# Reinhard.net
KiCad netlist of a schematic drawn in EAGLE
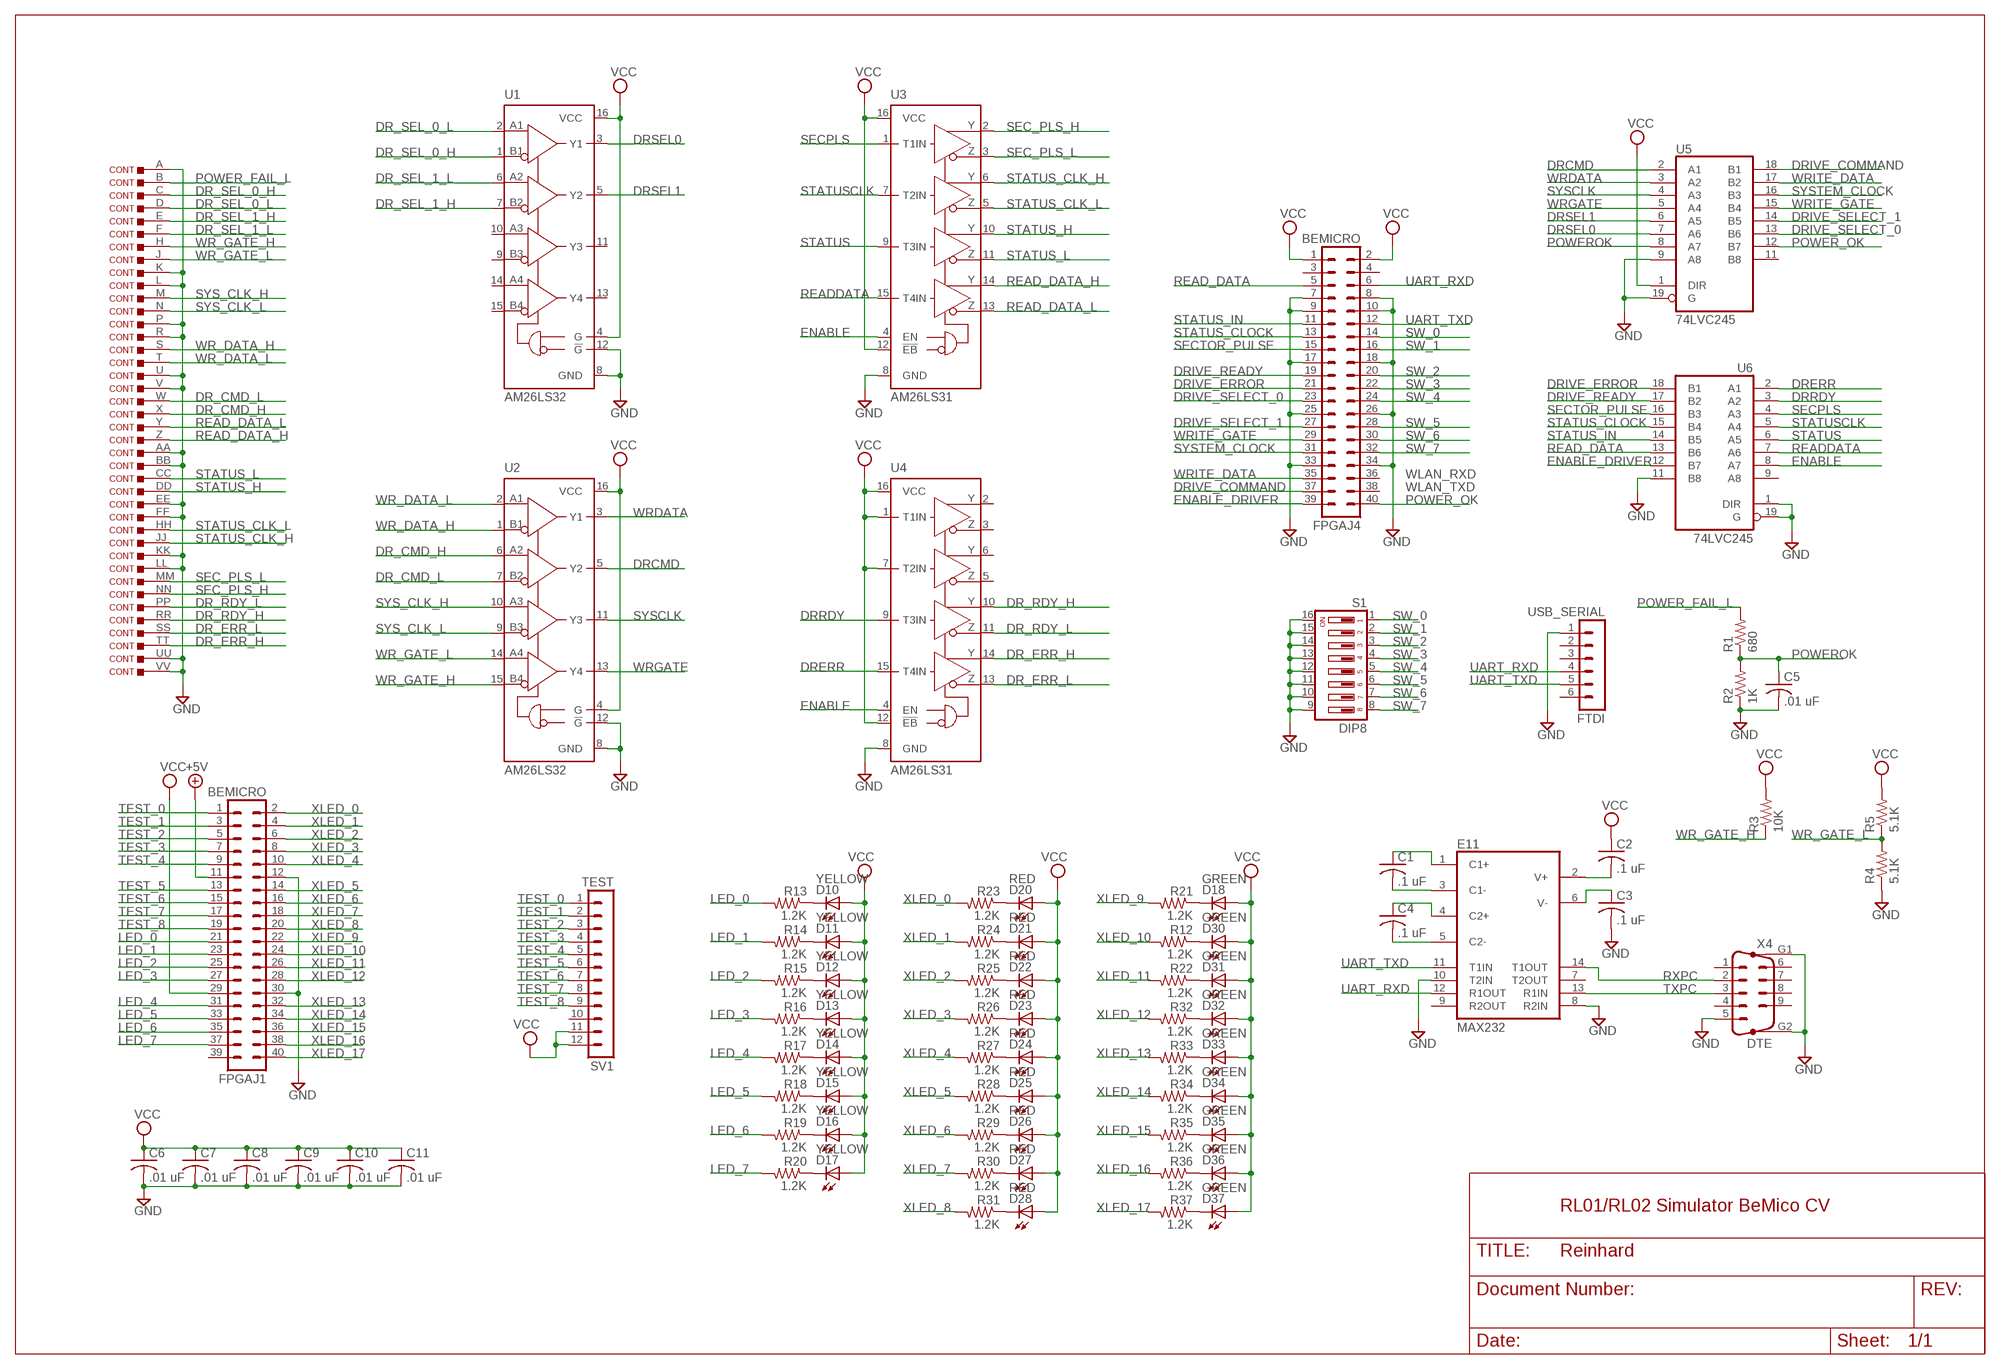
[diagram p0: schematic, sheet 1]

(export (version "E")
  (design (tool "Eeschema 10.0.6"))
  (components
    (comp (ref "C1")
      (value ".1 uF")
      (footprint "eagle-import:C050-025X075")
      (libsource (lib "eagle-import") (part "C-US050-025X075"))
    )
    (comp (ref "C2")
      (value ".1 uF")
      (footprint "eagle-import:C050-025X075")
      (libsource (lib "eagle-import") (part "C-US050-025X075"))
    )
    (comp (ref "C3")
      (value ".1 uF")
      (footprint "eagle-import:C050-025X075")
      (libsource (lib "eagle-import") (part "C-US050-025X075"))
    )
    (comp (ref "C4")
      (value ".1 uF")
      (footprint "eagle-import:C050-025X075")
      (libsource (lib "eagle-import") (part "C-US050-025X075"))
    )
    (comp (ref "C5")
      (value ".01 uF")
      (footprint "eagle-import:C050-025X075")
      (libsource (lib "eagle-import") (part "C-US050-025X075"))
    )
    (comp (ref "C6")
      (value ".01 uF")
      (footprint "eagle-import:C050-025X075")
      (libsource (lib "eagle-import") (part "C-US050-025X075"))
    )
    (comp (ref "C7")
      (value ".01 uF")
      (footprint "eagle-import:C050-025X075")
      (libsource (lib "eagle-import") (part "C-US050-025X075"))
    )
    (comp (ref "C8")
      (value ".01 uF")
      (footprint "eagle-import:C050-025X075")
      (libsource (lib "eagle-import") (part "C-US050-025X075"))
    )
    (comp (ref "C9")
      (value ".01 uF")
      (footprint "eagle-import:C050-025X075")
      (libsource (lib "eagle-import") (part "C-US050-025X075"))
    )
    (comp (ref "C10")
      (value ".01 uF")
      (footprint "eagle-import:C050-025X075")
      (libsource (lib "eagle-import") (part "C-US050-025X075"))
    )
    (comp (ref "C11")
      (value ".01 uF")
      (footprint "eagle-import:C050-025X075")
      (libsource (lib "eagle-import") (part "C-US050-025X075"))
    )
    (comp (ref "CONT")
      (value "DEC40PINSV")
      (footprint "eagle-import:DEC40PINV")
      (libsource (lib "eagle-import") (part "DEC40PINSV"))
    )
    (comp (ref "D10")
      (value "YELLOW")
      (footprint "eagle-import:LED3MM")
      (libsource (lib "eagle-import") (part "LED3MM"))
    )
    (comp (ref "D11")
      (value "YELLOW")
      (footprint "eagle-import:LED3MM")
      (libsource (lib "eagle-import") (part "LED3MM"))
    )
    (comp (ref "D12")
      (value "YELLOW")
      (footprint "eagle-import:LED3MM")
      (libsource (lib "eagle-import") (part "LED3MM"))
    )
    (comp (ref "D13")
      (value "YELLOW")
      (footprint "eagle-import:LED3MM")
      (libsource (lib "eagle-import") (part "LED3MM"))
    )
    (comp (ref "D14")
      (value "YELLOW")
      (footprint "eagle-import:LED3MM")
      (libsource (lib "eagle-import") (part "LED3MM"))
    )
    (comp (ref "D15")
      (value "YELLOW")
      (footprint "eagle-import:LED3MM")
      (libsource (lib "eagle-import") (part "LED3MM"))
    )
    (comp (ref "D16")
      (value "YELLOW")
      (footprint "eagle-import:LED3MM")
      (libsource (lib "eagle-import") (part "LED3MM"))
    )
    (comp (ref "D17")
      (value "YELLOW")
      (footprint "eagle-import:LED3MM")
      (libsource (lib "eagle-import") (part "LED3MM"))
    )
    (comp (ref "D18")
      (value "GREEN")
      (footprint "eagle-import:LED3MM")
      (libsource (lib "eagle-import") (part "LED3MM"))
    )
    (comp (ref "D20")
      (value "RED")
      (footprint "eagle-import:LED3MM")
      (libsource (lib "eagle-import") (part "LED3MM"))
    )
    (comp (ref "D21")
      (value "RED")
      (footprint "eagle-import:LED3MM")
      (libsource (lib "eagle-import") (part "LED3MM"))
    )
    (comp (ref "D22")
      (value "RED")
      (footprint "eagle-import:LED3MM")
      (libsource (lib "eagle-import") (part "LED3MM"))
    )
    (comp (ref "D23")
      (value "RED")
      (footprint "eagle-import:LED3MM")
      (libsource (lib "eagle-import") (part "LED3MM"))
    )
    (comp (ref "D24")
      (value "RED")
      (footprint "eagle-import:LED3MM")
      (libsource (lib "eagle-import") (part "LED3MM"))
    )
    (comp (ref "D25")
      (value "RED")
      (footprint "eagle-import:LED3MM")
      (libsource (lib "eagle-import") (part "LED3MM"))
    )
    (comp (ref "D26")
      (value "RED")
      (footprint "eagle-import:LED3MM")
      (libsource (lib "eagle-import") (part "LED3MM"))
    )
    (comp (ref "D27")
      (value "RED")
      (footprint "eagle-import:LED3MM")
      (libsource (lib "eagle-import") (part "LED3MM"))
    )
    (comp (ref "D28")
      (value "RED")
      (footprint "eagle-import:LED3MM")
      (libsource (lib "eagle-import") (part "LED3MM"))
    )
    (comp (ref "D30")
      (value "GREEN")
      (footprint "eagle-import:LED3MM")
      (libsource (lib "eagle-import") (part "LED3MM"))
    )
    (comp (ref "D31")
      (value "GREEN")
      (footprint "eagle-import:LED3MM")
      (libsource (lib "eagle-import") (part "LED3MM"))
    )
    (comp (ref "D32")
      (value "GREEN")
      (footprint "eagle-import:LED3MM")
      (libsource (lib "eagle-import") (part "LED3MM"))
    )
    (comp (ref "D33")
      (value "GREEN")
      (footprint "eagle-import:LED3MM")
      (libsource (lib "eagle-import") (part "LED3MM"))
    )
    (comp (ref "D34")
      (value "GREEN")
      (footprint "eagle-import:LED3MM")
      (libsource (lib "eagle-import") (part "LED3MM"))
    )
    (comp (ref "D35")
      (value "GREEN")
      (footprint "eagle-import:LED3MM")
      (libsource (lib "eagle-import") (part "LED3MM"))
    )
    (comp (ref "D36")
      (value "GREEN")
      (footprint "eagle-import:LED3MM")
      (libsource (lib "eagle-import") (part "LED3MM"))
    )
    (comp (ref "D37")
      (value "GREEN")
      (footprint "eagle-import:LED3MM")
      (libsource (lib "eagle-import") (part "LED3MM"))
    )
    (comp (ref "E11")
      (value "MAX232")
      (footprint "eagle-import:DIL16")
      (fields (field (name "MF") "MAXIM") (field (name "MPN") "MAX232ACPE+"))
      (libsource (lib "eagle-import") (part "MAX232"))
    )
    (comp (ref "FPGAJ1")
      (value "BEMICRO")
      (footprint "eagle-import:MA20-2")
      (libsource (lib "eagle-import") (part "MA20-2"))
    )
    (comp (ref "FPGAJ4")
      (value "BEMICRO")
      (footprint "eagle-import:MA20-2")
      (libsource (lib "eagle-import") (part "MA20-2"))
    )
    (comp (ref "FTDI")
      (value "USB_SERIAL")
      (footprint "eagle-import:MA06-1")
      (libsource (lib "eagle-import") (part "MA06-1"))
    )
    (comp (ref "R1")
      (value "680")
      (footprint "eagle-import:0207_10")
      (libsource (lib "eagle-import") (part "R-US_0207/10"))
    )
    (comp (ref "R2")
      (value "1K")
      (footprint "eagle-import:0207_10")
      (libsource (lib "eagle-import") (part "R-US_0207/10"))
    )
    (comp (ref "R3")
      (value "10K")
      (footprint "eagle-import:0207_10")
      (libsource (lib "eagle-import") (part "R-US_0207/10"))
    )
    (comp (ref "R4")
      (value "5.1K")
      (footprint "eagle-import:0207_10")
      (libsource (lib "eagle-import") (part "R-US_0207/10"))
    )
    (comp (ref "R5")
      (value "5.1K")
      (footprint "eagle-import:0207_10")
      (libsource (lib "eagle-import") (part "R-US_0207/10"))
    )
    (comp (ref "R12")
      (value "1.2K")
      (footprint "eagle-import:0207_10")
      (libsource (lib "eagle-import") (part "R-US_0207/10"))
    )
    (comp (ref "R13")
      (value "1.2K")
      (footprint "eagle-import:0207_10")
      (libsource (lib "eagle-import") (part "R-US_0207/10"))
    )
    (comp (ref "R14")
      (value "1.2K")
      (footprint "eagle-import:0207_10")
      (libsource (lib "eagle-import") (part "R-US_0207/10"))
    )
    (comp (ref "R15")
      (value "1.2K")
      (footprint "eagle-import:0207_10")
      (libsource (lib "eagle-import") (part "R-US_0207/10"))
    )
    (comp (ref "R16")
      (value "1.2K")
      (footprint "eagle-import:0207_10")
      (libsource (lib "eagle-import") (part "R-US_0207/10"))
    )
    (comp (ref "R17")
      (value "1.2K")
      (footprint "eagle-import:0207_10")
      (libsource (lib "eagle-import") (part "R-US_0207/10"))
    )
    (comp (ref "R18")
      (value "1.2K")
      (footprint "eagle-import:0207_10")
      (libsource (lib "eagle-import") (part "R-US_0207/10"))
    )
    (comp (ref "R19")
      (value "1.2K")
      (footprint "eagle-import:0207_10")
      (libsource (lib "eagle-import") (part "R-US_0207/10"))
    )
    (comp (ref "R20")
      (value "1.2K")
      (footprint "eagle-import:0207_10")
      (libsource (lib "eagle-import") (part "R-US_0207/10"))
    )
    (comp (ref "R21")
      (value "1.2K")
      (footprint "eagle-import:0207_10")
      (libsource (lib "eagle-import") (part "R-US_0207/10"))
    )
    (comp (ref "R22")
      (value "1.2K")
      (footprint "eagle-import:0207_10")
      (libsource (lib "eagle-import") (part "R-US_0207/10"))
    )
    (comp (ref "R23")
      (value "1.2K")
      (footprint "eagle-import:0207_10")
      (libsource (lib "eagle-import") (part "R-US_0207/10"))
    )
    (comp (ref "R24")
      (value "1.2K")
      (footprint "eagle-import:0207_10")
      (libsource (lib "eagle-import") (part "R-US_0207/10"))
    )
    (comp (ref "R25")
      (value "1.2K")
      (footprint "eagle-import:0207_10")
      (libsource (lib "eagle-import") (part "R-US_0207/10"))
    )
    (comp (ref "R26")
      (value "1.2K")
      (footprint "eagle-import:0207_10")
      (libsource (lib "eagle-import") (part "R-US_0207/10"))
    )
    (comp (ref "R27")
      (value "1.2K")
      (footprint "eagle-import:0207_10")
      (libsource (lib "eagle-import") (part "R-US_0207/10"))
    )
    (comp (ref "R28")
      (value "1.2K")
      (footprint "eagle-import:0207_10")
      (libsource (lib "eagle-import") (part "R-US_0207/10"))
    )
    (comp (ref "R29")
      (value "1.2K")
      (footprint "eagle-import:0207_10")
      (libsource (lib "eagle-import") (part "R-US_0207/10"))
    )
    (comp (ref "R30")
      (value "1.2K")
      (footprint "eagle-import:0207_10")
      (libsource (lib "eagle-import") (part "R-US_0207/10"))
    )
    (comp (ref "R31")
      (value "1.2K")
      (footprint "eagle-import:0207_10")
      (libsource (lib "eagle-import") (part "R-US_0207/10"))
    )
    (comp (ref "R32")
      (value "1.2K")
      (footprint "eagle-import:0207_10")
      (libsource (lib "eagle-import") (part "R-US_0207/10"))
    )
    (comp (ref "R33")
      (value "1.2K")
      (footprint "eagle-import:0207_10")
      (libsource (lib "eagle-import") (part "R-US_0207/10"))
    )
    (comp (ref "R34")
      (value "1.2K")
      (footprint "eagle-import:0207_10")
      (libsource (lib "eagle-import") (part "R-US_0207/10"))
    )
    (comp (ref "R35")
      (value "1.2K")
      (footprint "eagle-import:0207_10")
      (libsource (lib "eagle-import") (part "R-US_0207/10"))
    )
    (comp (ref "R36")
      (value "1.2K")
      (footprint "eagle-import:0207_10")
      (libsource (lib "eagle-import") (part "R-US_0207/10"))
    )
    (comp (ref "R37")
      (value "1.2K")
      (footprint "eagle-import:0207_10")
      (libsource (lib "eagle-import") (part "R-US_0207/10"))
    )
    (comp (ref "S1")
      (value "DIP8")
      (footprint "eagle-import:DIP08YL")
      (libsource (lib "eagle-import") (part "DIP08YL"))
    )
    (comp (ref "SV1")
      (value "TEST")
      (footprint "eagle-import:MA12-1")
      (libsource (lib "eagle-import") (part "MA12-1"))
    )
    (comp (ref "U1")
      (value "AM26LS32")
      (footprint "eagle-import:DIL16")
      (fields (field (name "MF") "MAXIM") (field (name "MPN") "MAX3095CPE+"))
      (libsource (lib "eagle-import") (part "MAX309PE5C"))
    )
    (comp (ref "U2")
      (value "AM26LS32")
      (footprint "eagle-import:DIL16")
      (fields (field (name "MF") "MAXIM") (field (name "MPN") "MAX3095CPE+"))
      (libsource (lib "eagle-import") (part "MAX309PE5C"))
    )
    (comp (ref "U3")
      (value "AM26LS31")
      (footprint "eagle-import:DIL16")
      (libsource (lib "eagle-import") (part "MAX304"))
    )
    (comp (ref "U4")
      (value "AM26LS31")
      (footprint "eagle-import:DIL16")
      (libsource (lib "eagle-import") (part "MAX304"))
    )
    (comp (ref "U5")
      (value "74LVC245")
      (footprint "eagle-import:DIL20")
      (libsource (lib "eagle-import") (part "74245NLS"))
    )
    (comp (ref "U6")
      (value "74LVC245")
      (footprint "eagle-import:DIL20")
      (libsource (lib "eagle-import") (part "74245NLS"))
    )
    (comp (ref "X4")
      (value "DTE")
      (footprint "eagle-import:M09HP")
      (libsource (lib "eagle-import") (part "M09HP"))
    )
  )
  (nets
    (net (code "1") (name "+5V") (class "Default")
      (node (ref "FPGAJ1") (pin "11") (pinfunction "11_11") (pintype "passive"))
    )
    (net (code "2") (name "/DRCMD") (class "Default")
      (node (ref "U2") (pin "5") (pinfunction "Y2_5") (pintype "output"))
      (node (ref "U5") (pin "2") (pinfunction "A1_2") (pintype "bidirectional"))
    )
    (net (code "3") (name "/DRERR") (class "Default")
      (node (ref "U4") (pin "15") (pinfunction "T4IN_15") (pintype "input"))
      (node (ref "U6") (pin "2") (pinfunction "A1_2") (pintype "bidirectional"))
    )
    (net (code "4") (name "/DRIVE_COMMAND") (class "Default")
      (node (ref "FPGAJ4") (pin "37") (pinfunction "37_37") (pintype "passive"))
      (node (ref "U5") (pin "18") (pinfunction "B1_18") (pintype "bidirectional"))
    )
    (net (code "5") (name "/DRIVE_ERROR") (class "Default")
      (node (ref "FPGAJ4") (pin "21") (pinfunction "21_21") (pintype "passive"))
      (node (ref "U6") (pin "18") (pinfunction "B1_18") (pintype "bidirectional"))
    )
    (net (code "6") (name "/DRIVE_READY") (class "Default")
      (node (ref "FPGAJ4") (pin "19") (pinfunction "19_19") (pintype "passive"))
      (node (ref "U6") (pin "17") (pinfunction "B2_17") (pintype "bidirectional"))
    )
    (net (code "7") (name "/DRIVE_SELECT_0") (class "Default")
      (node (ref "FPGAJ4") (pin "23") (pinfunction "23_23") (pintype "passive"))
      (node (ref "U5") (pin "13") (pinfunction "B6_13") (pintype "bidirectional"))
    )
    (net (code "8") (name "/DRIVE_SELECT_1") (class "Default")
      (node (ref "FPGAJ4") (pin "27") (pinfunction "27_27") (pintype "passive"))
      (node (ref "U5") (pin "14") (pinfunction "B5_14") (pintype "bidirectional"))
    )
    (net (code "9") (name "/DRRDY") (class "Default")
      (node (ref "U4") (pin "9") (pinfunction "T3IN_9") (pintype "input"))
      (node (ref "U6") (pin "3") (pinfunction "A2_3") (pintype "bidirectional"))
    )
    (net (code "10") (name "/DRSEL0") (class "Default")
      (node (ref "U1") (pin "3") (pinfunction "Y1_3") (pintype "output"))
      (node (ref "U5") (pin "7") (pinfunction "A6_7") (pintype "bidirectional"))
    )
    (net (code "11") (name "/DRSEL1") (class "Default")
      (node (ref "U1") (pin "5") (pinfunction "Y2_5") (pintype "output"))
      (node (ref "U5") (pin "6") (pinfunction "A5_6") (pintype "bidirectional"))
    )
    (net (code "12") (name "/DR_CMD_H") (class "Default")
      (node (ref "CONT") (pin "X") (pinfunction "P$2_X") (pintype "passive"))
      (node (ref "U2") (pin "6") (pinfunction "A2_6") (pintype "output"))
    )
    (net (code "13") (name "/DR_CMD_L") (class "Default")
      (node (ref "CONT") (pin "W") (pinfunction "P$2_W") (pintype "passive"))
      (node (ref "U2") (pin "7") (pinfunction "B2_7") (pintype "output"))
    )
    (net (code "14") (name "/DR_ERR_H") (class "Default")
      (node (ref "CONT") (pin "TT") (pinfunction "P$2_TT") (pintype "passive"))
      (node (ref "U4") (pin "14") (pinfunction "Y4_14") (pintype "output"))
    )
    (net (code "15") (name "/DR_ERR_L") (class "Default")
      (node (ref "CONT") (pin "SS") (pinfunction "P$2_SS") (pintype "passive"))
      (node (ref "U4") (pin "13") (pinfunction "Z4_13") (pintype "output"))
    )
    (net (code "16") (name "/DR_RDY_H") (class "Default")
      (node (ref "CONT") (pin "RR") (pinfunction "P$2_RR") (pintype "passive"))
      (node (ref "U4") (pin "10") (pinfunction "Y3_10") (pintype "output"))
    )
    (net (code "17") (name "/DR_RDY_L") (class "Default")
      (node (ref "CONT") (pin "PP") (pinfunction "P$2_PP") (pintype "passive"))
      (node (ref "U4") (pin "11") (pinfunction "Z3_11") (pintype "output"))
    )
    (net (code "18") (name "/DR_SEL_0_H") (class "Default")
      (node (ref "CONT") (pin "C") (pinfunction "P$2_C") (pintype "passive"))
      (node (ref "U1") (pin "1") (pinfunction "B1_1") (pintype "output"))
    )
    (net (code "19") (name "/DR_SEL_0_L") (class "Default")
      (node (ref "CONT") (pin "D") (pinfunction "P$2_D") (pintype "passive"))
      (node (ref "U1") (pin "2") (pinfunction "A1_2") (pintype "output"))
    )
    (net (code "20") (name "/DR_SEL_1_H") (class "Default")
      (node (ref "CONT") (pin "E") (pinfunction "P$2_E") (pintype "passive"))
      (node (ref "U1") (pin "7") (pinfunction "B2_7") (pintype "output"))
    )
    (net (code "21") (name "/DR_SEL_1_L") (class "Default")
      (node (ref "CONT") (pin "F") (pinfunction "P$2_F") (pintype "passive"))
      (node (ref "U1") (pin "6") (pinfunction "A2_6") (pintype "output"))
    )
    (net (code "22") (name "/ENABLE") (class "Default")
      (node (ref "U3") (pin "4") (pinfunction "EN_4") (pintype "input"))
      (node (ref "U4") (pin "4") (pinfunction "EN_4") (pintype "input"))
      (node (ref "U6") (pin "8") (pinfunction "A7_8") (pintype "bidirectional"))
    )
    (net (code "23") (name "/ENABLE_DRIVER") (class "Default")
      (node (ref "FPGAJ4") (pin "39") (pinfunction "39_39") (pintype "passive"))
      (node (ref "U6") (pin "12") (pinfunction "B7_12") (pintype "bidirectional"))
    )
    (net (code "24") (name "/LED_0") (class "Default")
      (node (ref "FPGAJ1") (pin "21") (pinfunction "21_21") (pintype "passive"))
      (node (ref "R13") (pin "2") (pinfunction "2_2") (pintype "passive"))
    )
    (net (code "25") (name "/LED_1") (class "Default")
      (node (ref "FPGAJ1") (pin "23") (pinfunction "23_23") (pintype "passive"))
      (node (ref "R14") (pin "2") (pinfunction "2_2") (pintype "passive"))
    )
    (net (code "26") (name "/LED_2") (class "Default")
      (node (ref "FPGAJ1") (pin "25") (pinfunction "25_25") (pintype "passive"))
      (node (ref "R15") (pin "2") (pinfunction "2_2") (pintype "passive"))
    )
    (net (code "27") (name "/LED_3") (class "Default")
      (node (ref "FPGAJ1") (pin "27") (pinfunction "27_27") (pintype "passive"))
      (node (ref "R16") (pin "2") (pinfunction "2_2") (pintype "passive"))
    )
    (net (code "28") (name "/LED_4") (class "Default")
      (node (ref "FPGAJ1") (pin "31") (pinfunction "31_31") (pintype "passive"))
      (node (ref "R17") (pin "2") (pinfunction "2_2") (pintype "passive"))
    )
    (net (code "29") (name "/LED_5") (class "Default")
      (node (ref "FPGAJ1") (pin "33") (pinfunction "33_33") (pintype "passive"))
      (node (ref "R18") (pin "2") (pinfunction "2_2") (pintype "passive"))
    )
    (net (code "30") (name "/LED_6") (class "Default")
      (node (ref "FPGAJ1") (pin "35") (pinfunction "35_35") (pintype "passive"))
      (node (ref "R19") (pin "2") (pinfunction "2_2") (pintype "passive"))
    )
    (net (code "31") (name "/LED_7") (class "Default")
      (node (ref "FPGAJ1") (pin "37") (pinfunction "37_37") (pintype "passive"))
      (node (ref "R20") (pin "2") (pinfunction "2_2") (pintype "passive"))
    )
    (net (code "32") (name "/POWEROK") (class "Default")
      (node (ref "C5") (pin "1") (pinfunction "1_1") (pintype "passive"))
      (node (ref "R1") (pin "1") (pinfunction "1_1") (pintype "passive"))
      (node (ref "R2") (pin "2") (pinfunction "2_2") (pintype "passive"))
      (node (ref "U5") (pin "8") (pinfunction "A7_8") (pintype "bidirectional"))
    )
    (net (code "33") (name "/POWER_FAIL_L") (class "Default")
      (node (ref "CONT") (pin "B") (pinfunction "P$2_B") (pintype "passive"))
      (node (ref "R1") (pin "2") (pinfunction "2_2") (pintype "passive"))
    )
    (net (code "34") (name "/POWER_OK") (class "Default")
      (node (ref "FPGAJ4") (pin "40") (pinfunction "40_40") (pintype "passive"))
      (node (ref "U5") (pin "12") (pinfunction "B7_12") (pintype "bidirectional"))
    )
    (net (code "35") (name "/READDATA") (class "Default")
      (node (ref "U3") (pin "15") (pinfunction "T4IN_15") (pintype "input"))
      (node (ref "U6") (pin "7") (pinfunction "A6_7") (pintype "bidirectional"))
    )
    (net (code "36") (name "/READ_DATA") (class "Default")
      (node (ref "FPGAJ4") (pin "5") (pinfunction "5_5") (pintype "passive"))
      (node (ref "U6") (pin "13") (pinfunction "B6_13") (pintype "bidirectional"))
    )
    (net (code "37") (name "/READ_DATA_H") (class "Default")
      (node (ref "CONT") (pin "Z") (pinfunction "P$2_Z") (pintype "passive"))
      (node (ref "U3") (pin "14") (pinfunction "Y4_14") (pintype "output"))
    )
    (net (code "38") (name "/READ_DATA_L") (class "Default")
      (node (ref "CONT") (pin "Y") (pinfunction "P$2_Y") (pintype "passive"))
      (node (ref "U3") (pin "13") (pinfunction "Z4_13") (pintype "output"))
    )
    (net (code "39") (name "/RXPC") (class "Default")
      (node (ref "E11") (pin "14") (pinfunction "T1OUT_14") (pintype "output"))
      (node (ref "X4") (pin "2") (pinfunction "2_2") (pintype "passive"))
    )
    (net (code "40") (name "/SECPLS") (class "Default")
      (node (ref "U3") (pin "1") (pinfunction "T1IN_1") (pintype "input"))
      (node (ref "U6") (pin "4") (pinfunction "A3_4") (pintype "bidirectional"))
    )
    (net (code "41") (name "/SECTOR_PULSE") (class "Default")
      (node (ref "FPGAJ4") (pin "15") (pinfunction "15_15") (pintype "passive"))
      (node (ref "U6") (pin "16") (pinfunction "B3_16") (pintype "bidirectional"))
    )
    (net (code "42") (name "/SEC_PLS_H") (class "Default")
      (node (ref "CONT") (pin "NN") (pinfunction "P$2_NN") (pintype "passive"))
      (node (ref "U3") (pin "2") (pinfunction "Y1_2") (pintype "output"))
    )
    (net (code "43") (name "/SEC_PLS_L") (class "Default")
      (node (ref "CONT") (pin "MM") (pinfunction "P$2_MM") (pintype "passive"))
      (node (ref "U3") (pin "3") (pinfunction "Z1_3") (pintype "output"))
    )
    (net (code "44") (name "/STATUS") (class "Default")
      (node (ref "U3") (pin "9") (pinfunction "T3IN_9") (pintype "input"))
      (node (ref "U6") (pin "6") (pinfunction "A5_6") (pintype "bidirectional"))
    )
    (net (code "45") (name "/STATUSCLK") (class "Default")
      (node (ref "U3") (pin "7") (pinfunction "T2IN_7") (pintype "input"))
      (node (ref "U6") (pin "5") (pinfunction "A4_5") (pintype "bidirectional"))
    )
    (net (code "46") (name "/STATUS_CLK_H") (class "Default")
      (node (ref "CONT") (pin "JJ") (pinfunction "P$2_JJ") (pintype "passive"))
      (node (ref "U3") (pin "6") (pinfunction "Y2_6") (pintype "output"))
    )
    (net (code "47") (name "/STATUS_CLK_L") (class "Default")
      (node (ref "CONT") (pin "HH") (pinfunction "P$2_HH") (pintype "passive"))
      (node (ref "U3") (pin "5") (pinfunction "Z2_5") (pintype "output"))
    )
    (net (code "48") (name "/STATUS_CLOCK") (class "Default")
      (node (ref "FPGAJ4") (pin "13") (pinfunction "13_13") (pintype "passive"))
      (node (ref "U6") (pin "15") (pinfunction "B4_15") (pintype "bidirectional"))
    )
    (net (code "49") (name "/STATUS_H") (class "Default")
      (node (ref "CONT") (pin "DD") (pinfunction "P$2_DD") (pintype "passive"))
      (node (ref "U3") (pin "10") (pinfunction "Y3_10") (pintype "output"))
    )
    (net (code "50") (name "/STATUS_IN") (class "Default")
      (node (ref "FPGAJ4") (pin "11") (pinfunction "11_11") (pintype "passive"))
      (node (ref "U6") (pin "14") (pinfunction "B5_14") (pintype "bidirectional"))
    )
    (net (code "51") (name "/STATUS_L") (class "Default")
      (node (ref "CONT") (pin "CC") (pinfunction "P$2_CC") (pintype "passive"))
      (node (ref "U3") (pin "11") (pinfunction "Z3_11") (pintype "output"))
    )
    (net (code "52") (name "/SW_0") (class "Default")
      (node (ref "FPGAJ4") (pin "14") (pinfunction "14_14") (pintype "passive"))
      (node (ref "S1") (pin "1") (pinfunction "1_1") (pintype "passive"))
    )
    (net (code "53") (name "/SW_1") (class "Default")
      (node (ref "FPGAJ4") (pin "16") (pinfunction "16_16") (pintype "passive"))
      (node (ref "S1") (pin "2") (pinfunction "2_2") (pintype "passive"))
    )
    (net (code "54") (name "/SW_2") (class "Default")
      (node (ref "FPGAJ4") (pin "20") (pinfunction "20_20") (pintype "passive"))
      (node (ref "S1") (pin "3") (pinfunction "3_3") (pintype "passive"))
    )
    (net (code "55") (name "/SW_3") (class "Default")
      (node (ref "FPGAJ4") (pin "22") (pinfunction "22_22") (pintype "passive"))
      (node (ref "S1") (pin "4") (pinfunction "4_4") (pintype "passive"))
    )
    (net (code "56") (name "/SW_4") (class "Default")
      (node (ref "FPGAJ4") (pin "24") (pinfunction "24_24") (pintype "passive"))
      (node (ref "S1") (pin "5") (pinfunction "5_5") (pintype "passive"))
    )
    (net (code "57") (name "/SW_5") (class "Default")
      (node (ref "FPGAJ4") (pin "28") (pinfunction "28_28") (pintype "passive"))
      (node (ref "S1") (pin "6") (pinfunction "6_6") (pintype "passive"))
    )
    (net (code "58") (name "/SW_6") (class "Default")
      (node (ref "FPGAJ4") (pin "30") (pinfunction "30_30") (pintype "passive"))
      (node (ref "S1") (pin "7") (pinfunction "7_7") (pintype "passive"))
    )
    (net (code "59") (name "/SW_7") (class "Default")
      (node (ref "FPGAJ4") (pin "32") (pinfunction "32_32") (pintype "passive"))
      (node (ref "S1") (pin "8") (pinfunction "8_8") (pintype "passive"))
    )
    (net (code "60") (name "/SYSCLK") (class "Default")
      (node (ref "U2") (pin "11") (pinfunction "Y3_11") (pintype "output"))
      (node (ref "U5") (pin "4") (pinfunction "A3_4") (pintype "bidirectional"))
    )
    (net (code "61") (name "/SYSTEM_CLOCK") (class "Default")
      (node (ref "FPGAJ4") (pin "31") (pinfunction "31_31") (pintype "passive"))
      (node (ref "U5") (pin "16") (pinfunction "B3_16") (pintype "bidirectional"))
    )
    (net (code "62") (name "/SYS_CLK_H") (class "Default")
      (node (ref "CONT") (pin "M") (pinfunction "P$2_M") (pintype "passive"))
      (node (ref "U2") (pin "10") (pinfunction "A3_10") (pintype "output"))
    )
    (net (code "63") (name "/SYS_CLK_L") (class "Default")
      (node (ref "CONT") (pin "N") (pinfunction "P$2_N") (pintype "passive"))
      (node (ref "U2") (pin "9") (pinfunction "B3_9") (pintype "output"))
    )
    (net (code "64") (name "/TEST_0") (class "Default")
      (node (ref "FPGAJ1") (pin "1") (pinfunction "1_1") (pintype "passive"))
      (node (ref "SV1") (pin "1") (pinfunction "1_1") (pintype "passive"))
    )
    (net (code "65") (name "/TEST_1") (class "Default")
      (node (ref "FPGAJ1") (pin "3") (pinfunction "3_3") (pintype "passive"))
      (node (ref "SV1") (pin "2") (pinfunction "2_2") (pintype "passive"))
    )
    (net (code "66") (name "/TEST_2") (class "Default")
      (node (ref "FPGAJ1") (pin "5") (pinfunction "5_5") (pintype "passive"))
      (node (ref "SV1") (pin "3") (pinfunction "3_3") (pintype "passive"))
    )
    (net (code "67") (name "/TEST_3") (class "Default")
      (node (ref "FPGAJ1") (pin "7") (pinfunction "7_7") (pintype "passive"))
      (node (ref "SV1") (pin "4") (pinfunction "4_4") (pintype "passive"))
    )
    (net (code "68") (name "/TEST_4") (class "Default")
      (node (ref "FPGAJ1") (pin "9") (pinfunction "9_9") (pintype "passive"))
      (node (ref "SV1") (pin "5") (pinfunction "5_5") (pintype "passive"))
    )
    (net (code "69") (name "/TEST_5") (class "Default")
      (node (ref "FPGAJ1") (pin "13") (pinfunction "13_13") (pintype "passive"))
      (node (ref "SV1") (pin "6") (pinfunction "6_6") (pintype "passive"))
    )
    (net (code "70") (name "/TEST_6") (class "Default")
      (node (ref "FPGAJ1") (pin "15") (pinfunction "15_15") (pintype "passive"))
      (node (ref "SV1") (pin "7") (pinfunction "7_7") (pintype "passive"))
    )
    (net (code "71") (name "/TEST_7") (class "Default")
      (node (ref "FPGAJ1") (pin "17") (pinfunction "17_17") (pintype "passive"))
      (node (ref "SV1") (pin "8") (pinfunction "8_8") (pintype "passive"))
    )
    (net (code "72") (name "/TEST_8") (class "Default")
      (node (ref "FPGAJ1") (pin "19") (pinfunction "19_19") (pintype "passive"))
      (node (ref "SV1") (pin "9") (pinfunction "9_9") (pintype "passive"))
    )
    (net (code "73") (name "/TXPC") (class "Default")
      (node (ref "E11") (pin "13") (pinfunction "R1IN_13") (pintype "input"))
      (node (ref "X4") (pin "3") (pinfunction "3_3") (pintype "passive"))
    )
    (net (code "74") (name "/UART_RXD") (class "Default")
      (node (ref "E11") (pin "12") (pinfunction "R1OUT_12") (pintype "output"))
      (node (ref "FPGAJ4") (pin "6") (pinfunction "6_6") (pintype "passive"))
      (node (ref "FTDI") (pin "4") (pinfunction "4_4") (pintype "passive"))
    )
    (net (code "75") (name "/UART_TXD") (class "Default")
      (node (ref "E11") (pin "11") (pinfunction "T1IN_11") (pintype "input"))
      (node (ref "FPGAJ4") (pin "12") (pinfunction "12_12") (pintype "passive"))
      (node (ref "FTDI") (pin "5") (pinfunction "5_5") (pintype "passive"))
    )
    (net (code "76") (name "/WRDATA") (class "Default")
      (node (ref "U2") (pin "3") (pinfunction "Y1_3") (pintype "output"))
      (node (ref "U5") (pin "3") (pinfunction "A2_3") (pintype "bidirectional"))
    )
    (net (code "77") (name "/WRGATE") (class "Default")
      (node (ref "U2") (pin "13") (pinfunction "Y4_13") (pintype "output"))
      (node (ref "U5") (pin "5") (pinfunction "A4_5") (pintype "bidirectional"))
    )
    (net (code "78") (name "/WRITE_DATA") (class "Default")
      (node (ref "FPGAJ4") (pin "35") (pinfunction "35_35") (pintype "passive"))
      (node (ref "U5") (pin "17") (pinfunction "B2_17") (pintype "bidirectional"))
    )
    (net (code "79") (name "/WRITE_GATE") (class "Default")
      (node (ref "FPGAJ4") (pin "29") (pinfunction "29_29") (pintype "passive"))
      (node (ref "U5") (pin "15") (pinfunction "B4_15") (pintype "bidirectional"))
    )
    (net (code "80") (name "/WR_DATA_H") (class "Default")
      (node (ref "CONT") (pin "S") (pinfunction "P$2_S") (pintype "passive"))
      (node (ref "U2") (pin "1") (pinfunction "B1_1") (pintype "output"))
    )
    (net (code "81") (name "/WR_DATA_L") (class "Default")
      (node (ref "CONT") (pin "T") (pinfunction "P$2_T") (pintype "passive"))
      (node (ref "U2") (pin "2") (pinfunction "A1_2") (pintype "output"))
    )
    (net (code "82") (name "/WR_GATE_H") (class "Default")
      (node (ref "CONT") (pin "H") (pinfunction "P$2_H") (pintype "passive"))
      (node (ref "R3") (pin "1") (pinfunction "1_1") (pintype "passive"))
      (node (ref "U2") (pin "15") (pinfunction "B4_15") (pintype "output"))
    )
    (net (code "83") (name "/WR_GATE_L") (class "Default")
      (node (ref "CONT") (pin "J") (pinfunction "P$2_J") (pintype "passive"))
      (node (ref "R4") (pin "2") (pinfunction "2_2") (pintype "passive"))
      (node (ref "R5") (pin "1") (pinfunction "1_1") (pintype "passive"))
      (node (ref "U2") (pin "14") (pinfunction "A4_14") (pintype "output"))
    )
    (net (code "84") (name "/XLED_0") (class "Default")
      (node (ref "FPGAJ1") (pin "2") (pinfunction "2_2") (pintype "passive"))
      (node (ref "R23") (pin "2") (pinfunction "2_2") (pintype "passive"))
    )
    (net (code "85") (name "/XLED_1") (class "Default")
      (node (ref "FPGAJ1") (pin "4") (pinfunction "4_4") (pintype "passive"))
      (node (ref "R24") (pin "2") (pinfunction "2_2") (pintype "passive"))
    )
    (net (code "86") (name "/XLED_2") (class "Default")
      (node (ref "FPGAJ1") (pin "6") (pinfunction "6_6") (pintype "passive"))
      (node (ref "R25") (pin "2") (pinfunction "2_2") (pintype "passive"))
    )
    (net (code "87") (name "/XLED_3") (class "Default")
      (node (ref "FPGAJ1") (pin "8") (pinfunction "8_8") (pintype "passive"))
      (node (ref "R26") (pin "2") (pinfunction "2_2") (pintype "passive"))
    )
    (net (code "88") (name "/XLED_4") (class "Default")
      (node (ref "FPGAJ1") (pin "10") (pinfunction "10_10") (pintype "passive"))
      (node (ref "R27") (pin "2") (pinfunction "2_2") (pintype "passive"))
    )
    (net (code "89") (name "/XLED_5") (class "Default")
      (node (ref "FPGAJ1") (pin "14") (pinfunction "14_14") (pintype "passive"))
      (node (ref "R28") (pin "2") (pinfunction "2_2") (pintype "passive"))
    )
    (net (code "90") (name "/XLED_6") (class "Default")
      (node (ref "FPGAJ1") (pin "16") (pinfunction "16_16") (pintype "passive"))
      (node (ref "R29") (pin "2") (pinfunction "2_2") (pintype "passive"))
    )
    (net (code "91") (name "/XLED_7") (class "Default")
      (node (ref "FPGAJ1") (pin "18") (pinfunction "18_18") (pintype "passive"))
      (node (ref "R30") (pin "2") (pinfunction "2_2") (pintype "passive"))
    )
    (net (code "92") (name "/XLED_8") (class "Default")
      (node (ref "FPGAJ1") (pin "20") (pinfunction "20_20") (pintype "passive"))
      (node (ref "R31") (pin "2") (pinfunction "2_2") (pintype "passive"))
    )
    (net (code "93") (name "/XLED_9") (class "Default")
      (node (ref "FPGAJ1") (pin "22") (pinfunction "22_22") (pintype "passive"))
      (node (ref "R21") (pin "2") (pinfunction "2_2") (pintype "passive"))
    )
    (net (code "94") (name "/XLED_10") (class "Default")
      (node (ref "FPGAJ1") (pin "24") (pinfunction "24_24") (pintype "passive"))
      (node (ref "R12") (pin "2") (pinfunction "2_2") (pintype "passive"))
    )
    (net (code "95") (name "/XLED_11") (class "Default")
      (node (ref "FPGAJ1") (pin "26") (pinfunction "26_26") (pintype "passive"))
      (node (ref "R22") (pin "2") (pinfunction "2_2") (pintype "passive"))
    )
    (net (code "96") (name "/XLED_12") (class "Default")
      (node (ref "FPGAJ1") (pin "28") (pinfunction "28_28") (pintype "passive"))
      (node (ref "R32") (pin "2") (pinfunction "2_2") (pintype "passive"))
    )
    (net (code "97") (name "/XLED_13") (class "Default")
      (node (ref "FPGAJ1") (pin "32") (pinfunction "32_32") (pintype "passive"))
      (node (ref "R33") (pin "2") (pinfunction "2_2") (pintype "passive"))
    )
    (net (code "98") (name "/XLED_14") (class "Default")
      (node (ref "FPGAJ1") (pin "34") (pinfunction "34_34") (pintype "passive"))
      (node (ref "R34") (pin "2") (pinfunction "2_2") (pintype "passive"))
    )
    (net (code "99") (name "/XLED_15") (class "Default")
      (node (ref "FPGAJ1") (pin "36") (pinfunction "36_36") (pintype "passive"))
      (node (ref "R35") (pin "2") (pinfunction "2_2") (pintype "passive"))
    )
    (net (code "100") (name "/XLED_16") (class "Default")
      (node (ref "FPGAJ1") (pin "38") (pinfunction "38_38") (pintype "passive"))
      (node (ref "R36") (pin "2") (pinfunction "2_2") (pintype "passive"))
    )
    (net (code "101") (name "/XLED_17") (class "Default")
      (node (ref "FPGAJ1") (pin "40") (pinfunction "40_40") (pintype "passive"))
      (node (ref "R37") (pin "2") (pinfunction "2_2") (pintype "passive"))
    )
    (net (code "102") (name "GND") (class "Default")
      (node (ref "C10") (pin "2") (pinfunction "2_2") (pintype "passive"))
      (node (ref "C11") (pin "2") (pinfunction "2_2") (pintype "passive"))
      (node (ref "C3") (pin "2") (pinfunction "2_2") (pintype "passive"))
      (node (ref "C5") (pin "2") (pinfunction "2_2") (pintype "passive"))
      (node (ref "C6") (pin "2") (pinfunction "2_2") (pintype "passive"))
      (node (ref "C7") (pin "2") (pinfunction "2_2") (pintype "passive"))
      (node (ref "C8") (pin "2") (pinfunction "2_2") (pintype "passive"))
      (node (ref "C9") (pin "2") (pinfunction "2_2") (pintype "passive"))
      (node (ref "CONT") (pin "A") (pinfunction "P$2_A") (pintype "passive"))
      (node (ref "CONT") (pin "AA") (pinfunction "P$2_AA") (pintype "passive"))
      (node (ref "CONT") (pin "BB") (pinfunction "P$2_BB") (pintype "passive"))
      (node (ref "CONT") (pin "EE") (pinfunction "P$2_EE") (pintype "passive"))
      (node (ref "CONT") (pin "FF") (pinfunction "P$2_FF") (pintype "passive"))
      (node (ref "CONT") (pin "K") (pinfunction "P$2_K") (pintype "passive"))
      (node (ref "CONT") (pin "KK") (pinfunction "P$2_KK") (pintype "passive"))
      (node (ref "CONT") (pin "L") (pinfunction "P$2_L") (pintype "passive"))
      (node (ref "CONT") (pin "LL") (pinfunction "P$2_LL") (pintype "passive"))
      (node (ref "CONT") (pin "P") (pinfunction "P$2_P") (pintype "passive"))
      (node (ref "CONT") (pin "R") (pinfunction "P$2_R") (pintype "passive"))
      (node (ref "CONT") (pin "U") (pinfunction "P$2_U") (pintype "passive"))
      (node (ref "CONT") (pin "UU") (pinfunction "P$2_UU") (pintype "passive"))
      (node (ref "CONT") (pin "V") (pinfunction "P$2_V") (pintype "passive"))
      (node (ref "CONT") (pin "VV") (pinfunction "P$2_VV") (pintype "passive"))
      (node (ref "E11") (pin "10") (pinfunction "T2IN_10") (pintype "input"))
      (node (ref "E11") (pin "8") (pinfunction "R2IN_8") (pintype "input"))
      (node (ref "FPGAJ1") (pin "12") (pinfunction "12_12") (pintype "passive"))
      (node (ref "FPGAJ1") (pin "30") (pinfunction "30_30") (pintype "passive"))
      (node (ref "FPGAJ4") (pin "10") (pinfunction "10_10") (pintype "passive"))
      (node (ref "FPGAJ4") (pin "17") (pinfunction "17_17") (pintype "passive"))
      (node (ref "FPGAJ4") (pin "18") (pinfunction "18_18") (pintype "passive"))
      (node (ref "FPGAJ4") (pin "25") (pinfunction "25_25") (pintype "passive"))
      (node (ref "FPGAJ4") (pin "26") (pinfunction "26_26") (pintype "passive"))
      (node (ref "FPGAJ4") (pin "33") (pinfunction "33_33") (pintype "passive"))
      (node (ref "FPGAJ4") (pin "34") (pinfunction "34_34") (pintype "passive"))
      (node (ref "FPGAJ4") (pin "7") (pinfunction "7_7") (pintype "passive"))
      (node (ref "FPGAJ4") (pin "8") (pinfunction "8_8") (pintype "passive"))
      (node (ref "FPGAJ4") (pin "9") (pinfunction "9_9") (pintype "passive"))
      (node (ref "FTDI") (pin "1") (pinfunction "1_1") (pintype "passive"))
      (node (ref "R2") (pin "1") (pinfunction "1_1") (pintype "passive"))
      (node (ref "R4") (pin "1") (pinfunction "1_1") (pintype "passive"))
      (node (ref "S1") (pin "10") (pinfunction "10_10") (pintype "passive"))
      (node (ref "S1") (pin "11") (pinfunction "11_11") (pintype "passive"))
      (node (ref "S1") (pin "12") (pinfunction "12_12") (pintype "passive"))
      (node (ref "S1") (pin "13") (pinfunction "13_13") (pintype "passive"))
      (node (ref "S1") (pin "14") (pinfunction "14_14") (pintype "passive"))
      (node (ref "S1") (pin "15") (pinfunction "15_15") (pintype "passive"))
      (node (ref "S1") (pin "16") (pinfunction "16_16") (pintype "passive"))
      (node (ref "S1") (pin "9") (pinfunction "9_9") (pintype "passive"))
      (node (ref "U1") (pin "12") (pinfunction "~{G}_12") (pintype "input"))
      (node (ref "U1") (pin "8") (pinfunction "GND_8") (pintype "power_in"))
      (node (ref "U2") (pin "12") (pinfunction "~{G}_12") (pintype "input"))
      (node (ref "U2") (pin "8") (pinfunction "GND_8") (pintype "power_in"))
      (node (ref "U3") (pin "8") (pinfunction "GND_8") (pintype "power_in"))
      (node (ref "U4") (pin "8") (pinfunction "GND_8") (pintype "power_in"))
      (node (ref "U5") (pin "19") (pinfunction "G_19") (pintype "input"))
      (node (ref "U5") (pin "9") (pinfunction "A8_9") (pintype "bidirectional"))
      (node (ref "U6") (pin "1") (pinfunction "DIR_1") (pintype "input"))
      (node (ref "U6") (pin "11") (pinfunction "B8_11") (pintype "bidirectional"))
      (node (ref "U6") (pin "19") (pinfunction "G_19") (pintype "input"))
      (node (ref "X4") (pin "5") (pinfunction "5_5") (pintype "passive"))
      (node (ref "X4") (pin "G1") (pinfunction "G1_G1") (pintype "passive"))
      (node (ref "X4") (pin "G2") (pinfunction "G2_G2") (pintype "passive"))
    )
    (net (code "103") (name "Net-(D10-C)") (class "Default")
      (node (ref "D10") (pin "K") (pinfunction "C_K") (pintype "passive"))
      (node (ref "R13") (pin "1") (pinfunction "1_1") (pintype "passive"))
    )
    (net (code "104") (name "Net-(D11-C)") (class "Default")
      (node (ref "D11") (pin "K") (pinfunction "C_K") (pintype "passive"))
      (node (ref "R14") (pin "1") (pinfunction "1_1") (pintype "passive"))
    )
    (net (code "105") (name "Net-(D12-C)") (class "Default")
      (node (ref "D12") (pin "K") (pinfunction "C_K") (pintype "passive"))
      (node (ref "R15") (pin "1") (pinfunction "1_1") (pintype "passive"))
    )
    (net (code "106") (name "Net-(D13-C)") (class "Default")
      (node (ref "D13") (pin "K") (pinfunction "C_K") (pintype "passive"))
      (node (ref "R16") (pin "1") (pinfunction "1_1") (pintype "passive"))
    )
    (net (code "107") (name "Net-(D14-C)") (class "Default")
      (node (ref "D14") (pin "K") (pinfunction "C_K") (pintype "passive"))
      (node (ref "R17") (pin "1") (pinfunction "1_1") (pintype "passive"))
    )
    (net (code "108") (name "Net-(D15-C)") (class "Default")
      (node (ref "D15") (pin "K") (pinfunction "C_K") (pintype "passive"))
      (node (ref "R18") (pin "1") (pinfunction "1_1") (pintype "passive"))
    )
    (net (code "109") (name "Net-(D16-C)") (class "Default")
      (node (ref "D16") (pin "K") (pinfunction "C_K") (pintype "passive"))
      (node (ref "R19") (pin "1") (pinfunction "1_1") (pintype "passive"))
    )
    (net (code "110") (name "Net-(D17-C)") (class "Default")
      (node (ref "D17") (pin "K") (pinfunction "C_K") (pintype "passive"))
      (node (ref "R20") (pin "1") (pinfunction "1_1") (pintype "passive"))
    )
    (net (code "111") (name "Net-(D18-C)") (class "Default")
      (node (ref "D18") (pin "K") (pinfunction "C_K") (pintype "passive"))
      (node (ref "R21") (pin "1") (pinfunction "1_1") (pintype "passive"))
    )
    (net (code "112") (name "Net-(D20-C)") (class "Default")
      (node (ref "D20") (pin "K") (pinfunction "C_K") (pintype "passive"))
      (node (ref "R23") (pin "1") (pinfunction "1_1") (pintype "passive"))
    )
    (net (code "113") (name "Net-(D21-C)") (class "Default")
      (node (ref "D21") (pin "K") (pinfunction "C_K") (pintype "passive"))
      (node (ref "R24") (pin "1") (pinfunction "1_1") (pintype "passive"))
    )
    (net (code "114") (name "Net-(D22-C)") (class "Default")
      (node (ref "D22") (pin "K") (pinfunction "C_K") (pintype "passive"))
      (node (ref "R25") (pin "1") (pinfunction "1_1") (pintype "passive"))
    )
    (net (code "115") (name "Net-(D23-C)") (class "Default")
      (node (ref "D23") (pin "K") (pinfunction "C_K") (pintype "passive"))
      (node (ref "R26") (pin "1") (pinfunction "1_1") (pintype "passive"))
    )
    (net (code "116") (name "Net-(D24-C)") (class "Default")
      (node (ref "D24") (pin "K") (pinfunction "C_K") (pintype "passive"))
      (node (ref "R27") (pin "1") (pinfunction "1_1") (pintype "passive"))
    )
    (net (code "117") (name "Net-(D25-C)") (class "Default")
      (node (ref "D25") (pin "K") (pinfunction "C_K") (pintype "passive"))
      (node (ref "R28") (pin "1") (pinfunction "1_1") (pintype "passive"))
    )
    (net (code "118") (name "Net-(D26-C)") (class "Default")
      (node (ref "D26") (pin "K") (pinfunction "C_K") (pintype "passive"))
      (node (ref "R29") (pin "1") (pinfunction "1_1") (pintype "passive"))
    )
    (net (code "119") (name "Net-(D27-C)") (class "Default")
      (node (ref "D27") (pin "K") (pinfunction "C_K") (pintype "passive"))
      (node (ref "R30") (pin "1") (pinfunction "1_1") (pintype "passive"))
    )
    (net (code "120") (name "Net-(D28-C)") (class "Default")
      (node (ref "D28") (pin "K") (pinfunction "C_K") (pintype "passive"))
      (node (ref "R31") (pin "1") (pinfunction "1_1") (pintype "passive"))
    )
    (net (code "121") (name "Net-(D30-C)") (class "Default")
      (node (ref "D30") (pin "K") (pinfunction "C_K") (pintype "passive"))
      (node (ref "R12") (pin "1") (pinfunction "1_1") (pintype "passive"))
    )
    (net (code "122") (name "Net-(D31-C)") (class "Default")
      (node (ref "D31") (pin "K") (pinfunction "C_K") (pintype "passive"))
      (node (ref "R22") (pin "1") (pinfunction "1_1") (pintype "passive"))
    )
    (net (code "123") (name "Net-(D32-C)") (class "Default")
      (node (ref "D32") (pin "K") (pinfunction "C_K") (pintype "passive"))
      (node (ref "R32") (pin "1") (pinfunction "1_1") (pintype "passive"))
    )
    (net (code "124") (name "Net-(D33-C)") (class "Default")
      (node (ref "D33") (pin "K") (pinfunction "C_K") (pintype "passive"))
      (node (ref "R33") (pin "1") (pinfunction "1_1") (pintype "passive"))
    )
    (net (code "125") (name "Net-(D34-C)") (class "Default")
      (node (ref "D34") (pin "K") (pinfunction "C_K") (pintype "passive"))
      (node (ref "R34") (pin "1") (pinfunction "1_1") (pintype "passive"))
    )
    (net (code "126") (name "Net-(D35-C)") (class "Default")
      (node (ref "D35") (pin "K") (pinfunction "C_K") (pintype "passive"))
      (node (ref "R35") (pin "1") (pinfunction "1_1") (pintype "passive"))
    )
    (net (code "127") (name "Net-(D36-C)") (class "Default")
      (node (ref "D36") (pin "K") (pinfunction "C_K") (pintype "passive"))
      (node (ref "R36") (pin "1") (pinfunction "1_1") (pintype "passive"))
    )
    (net (code "128") (name "Net-(D37-C)") (class "Default")
      (node (ref "D37") (pin "K") (pinfunction "C_K") (pintype "passive"))
      (node (ref "R37") (pin "1") (pinfunction "1_1") (pintype "passive"))
    )
    (net (code "129") (name "Net-(E11A-C1+)") (class "Default")
      (node (ref "C1") (pin "1") (pinfunction "1_1") (pintype "passive"))
      (node (ref "E11") (pin "1") (pinfunction "C1+_1") (pintype "bidirectional"))
    )
    (net (code "130") (name "Net-(E11A-C1-)") (class "Default")
      (node (ref "C1") (pin "2") (pinfunction "2_2") (pintype "passive"))
      (node (ref "E11") (pin "3") (pinfunction "C1-_3") (pintype "bidirectional"))
    )
    (net (code "131") (name "Net-(E11A-C2+)") (class "Default")
      (node (ref "C4") (pin "1") (pinfunction "1_1") (pintype "passive"))
      (node (ref "E11") (pin "4") (pinfunction "C2+_4") (pintype "bidirectional"))
    )
    (net (code "132") (name "Net-(E11A-C2-)") (class "Default")
      (node (ref "C4") (pin "2") (pinfunction "2_2") (pintype "passive"))
      (node (ref "E11") (pin "5") (pinfunction "C2-_5") (pintype "bidirectional"))
    )
    (net (code "133") (name "Net-(E11A-V+)") (class "Default")
      (node (ref "C2") (pin "2") (pinfunction "2_2") (pintype "passive"))
      (node (ref "E11") (pin "2") (pinfunction "V+_2") (pintype "bidirectional"))
    )
    (net (code "134") (name "Net-(E11A-V-)") (class "Default")
      (node (ref "C3") (pin "1") (pinfunction "1_1") (pintype "passive"))
      (node (ref "E11") (pin "6") (pinfunction "V-_6") (pintype "bidirectional"))
    )
    (net (code "135") (name "VCC") (class "Default")
      (node (ref "C10") (pin "1") (pinfunction "1_1") (pintype "passive"))
      (node (ref "C11") (pin "1") (pinfunction "1_1") (pintype "passive"))
      (node (ref "C2") (pin "1") (pinfunction "1_1") (pintype "passive"))
      (node (ref "C6") (pin "1") (pinfunction "1_1") (pintype "passive"))
      (node (ref "C7") (pin "1") (pinfunction "1_1") (pintype "passive"))
      (node (ref "C8") (pin "1") (pinfunction "1_1") (pintype "passive"))
      (node (ref "C9") (pin "1") (pinfunction "1_1") (pintype "passive"))
      (node (ref "D10") (pin "A") (pinfunction "A_A") (pintype "passive"))
      (node (ref "D11") (pin "A") (pinfunction "A_A") (pintype "passive"))
      (node (ref "D12") (pin "A") (pinfunction "A_A") (pintype "passive"))
      (node (ref "D13") (pin "A") (pinfunction "A_A") (pintype "passive"))
      (node (ref "D14") (pin "A") (pinfunction "A_A") (pintype "passive"))
      (node (ref "D15") (pin "A") (pinfunction "A_A") (pintype "passive"))
      (node (ref "D16") (pin "A") (pinfunction "A_A") (pintype "passive"))
      (node (ref "D17") (pin "A") (pinfunction "A_A") (pintype "passive"))
      (node (ref "D18") (pin "A") (pinfunction "A_A") (pintype "passive"))
      (node (ref "D20") (pin "A") (pinfunction "A_A") (pintype "passive"))
      (node (ref "D21") (pin "A") (pinfunction "A_A") (pintype "passive"))
      (node (ref "D22") (pin "A") (pinfunction "A_A") (pintype "passive"))
      (node (ref "D23") (pin "A") (pinfunction "A_A") (pintype "passive"))
      (node (ref "D24") (pin "A") (pinfunction "A_A") (pintype "passive"))
      (node (ref "D25") (pin "A") (pinfunction "A_A") (pintype "passive"))
      (node (ref "D26") (pin "A") (pinfunction "A_A") (pintype "passive"))
      (node (ref "D27") (pin "A") (pinfunction "A_A") (pintype "passive"))
      (node (ref "D28") (pin "A") (pinfunction "A_A") (pintype "passive"))
      (node (ref "D30") (pin "A") (pinfunction "A_A") (pintype "passive"))
      (node (ref "D31") (pin "A") (pinfunction "A_A") (pintype "passive"))
      (node (ref "D32") (pin "A") (pinfunction "A_A") (pintype "passive"))
      (node (ref "D33") (pin "A") (pinfunction "A_A") (pintype "passive"))
      (node (ref "D34") (pin "A") (pinfunction "A_A") (pintype "passive"))
      (node (ref "D35") (pin "A") (pinfunction "A_A") (pintype "passive"))
      (node (ref "D36") (pin "A") (pinfunction "A_A") (pintype "passive"))
      (node (ref "D37") (pin "A") (pinfunction "A_A") (pintype "passive"))
      (node (ref "FPGAJ1") (pin "29") (pinfunction "29_29") (pintype "passive"))
      (node (ref "FPGAJ4") (pin "1") (pinfunction "1_1") (pintype "passive"))
      (node (ref "FPGAJ4") (pin "2") (pinfunction "2_2") (pintype "passive"))
      (node (ref "R3") (pin "2") (pinfunction "2_2") (pintype "passive"))
      (node (ref "R5") (pin "2") (pinfunction "2_2") (pintype "passive"))
      (node (ref "SV1") (pin "11") (pinfunction "11_11") (pintype "passive"))
      (node (ref "SV1") (pin "12") (pinfunction "12_12") (pintype "passive"))
      (node (ref "U1") (pin "16") (pinfunction "VCC_16") (pintype "power_in"))
      (node (ref "U1") (pin "4") (pinfunction "G_4") (pintype "input"))
      (node (ref "U2") (pin "16") (pinfunction "VCC_16") (pintype "power_in"))
      (node (ref "U2") (pin "4") (pinfunction "G_4") (pintype "input"))
      (node (ref "U3") (pin "12") (pinfunction "~{EB}_12") (pintype "input"))
      (node (ref "U3") (pin "16") (pinfunction "VCC_16") (pintype "power_in"))
      (node (ref "U4") (pin "1") (pinfunction "T1IN_1") (pintype "input"))
      (node (ref "U4") (pin "12") (pinfunction "~{EB}_12") (pintype "input"))
      (node (ref "U4") (pin "16") (pinfunction "VCC_16") (pintype "power_in"))
      (node (ref "U4") (pin "7") (pinfunction "T2IN_7") (pintype "input"))
      (node (ref "U5") (pin "1") (pinfunction "DIR_1") (pintype "input"))
    )
    (net (code "136") (name "unconnected-(E11A-R2OUT-Pad9)") (class "Default")
      (node (ref "E11") (pin "9") (pinfunction "R2OUT_9") (pintype "output"))
    )
    (net (code "137") (name "unconnected-(E11A-T2OUT-Pad7)") (class "Default")
      (node (ref "E11") (pin "7") (pinfunction "T2OUT_7") (pintype "output"))
    )
    (net (code "138") (name "unconnected-(FPGAJ1-Pad39)") (class "Default")
      (node (ref "FPGAJ1") (pin "39") (pinfunction "39_39") (pintype "passive"))
    )
    (net (code "139") (name "unconnected-(FPGAJ4-Pad3)") (class "Default")
      (node (ref "FPGAJ4") (pin "3") (pinfunction "3_3") (pintype "passive"))
    )
    (net (code "140") (name "unconnected-(FPGAJ4-Pad4)") (class "Default")
      (node (ref "FPGAJ4") (pin "4") (pinfunction "4_4") (pintype "passive"))
    )
    (net (code "141") (name "unconnected-(FPGAJ4-Pad36)") (class "Default")
      (node (ref "FPGAJ4") (pin "36") (pinfunction "36_36") (pintype "passive"))
    )
    (net (code "142") (name "unconnected-(FPGAJ4-Pad38)") (class "Default")
      (node (ref "FPGAJ4") (pin "38") (pinfunction "38_38") (pintype "passive"))
    )
    (net (code "143") (name "unconnected-(FTDI-Pad2)") (class "Default")
      (node (ref "FTDI") (pin "2") (pinfunction "2_2") (pintype "passive"))
    )
    (net (code "144") (name "unconnected-(FTDI-Pad3)") (class "Default")
      (node (ref "FTDI") (pin "3") (pinfunction "3_3") (pintype "passive"))
    )
    (net (code "145") (name "unconnected-(FTDI-Pad6)") (class "Default")
      (node (ref "FTDI") (pin "6") (pinfunction "6_6") (pintype "passive"))
    )
    (net (code "146") (name "unconnected-(SV1-Pad10)") (class "Default")
      (node (ref "SV1") (pin "10") (pinfunction "10_10") (pintype "passive"))
    )
    (net (code "147") (name "unconnected-(U1-A3-Pad10)") (class "Default")
      (node (ref "U1") (pin "10") (pinfunction "A3_10") (pintype "output"))
    )
    (net (code "148") (name "unconnected-(U1-A4-Pad14)") (class "Default")
      (node (ref "U1") (pin "14") (pinfunction "A4_14") (pintype "output"))
    )
    (net (code "149") (name "unconnected-(U1-B3-Pad9)") (class "Default")
      (node (ref "U1") (pin "9") (pinfunction "B3_9") (pintype "output"))
    )
    (net (code "150") (name "unconnected-(U1-B4-Pad15)") (class "Default")
      (node (ref "U1") (pin "15") (pinfunction "B4_15") (pintype "output"))
    )
    (net (code "151") (name "unconnected-(U1-Y3-Pad11)") (class "Default")
      (node (ref "U1") (pin "11") (pinfunction "Y3_11") (pintype "output"))
    )
    (net (code "152") (name "unconnected-(U1-Y4-Pad13)") (class "Default")
      (node (ref "U1") (pin "13") (pinfunction "Y4_13") (pintype "output"))
    )
    (net (code "153") (name "unconnected-(U4-Y1-Pad2)") (class "Default")
      (node (ref "U4") (pin "2") (pinfunction "Y1_2") (pintype "output"))
    )
    (net (code "154") (name "unconnected-(U4-Y2-Pad6)") (class "Default")
      (node (ref "U4") (pin "6") (pinfunction "Y2_6") (pintype "output"))
    )
    (net (code "155") (name "unconnected-(U4-Z1-Pad3)") (class "Default")
      (node (ref "U4") (pin "3") (pinfunction "Z1_3") (pintype "output"))
    )
    (net (code "156") (name "unconnected-(U4-Z2-Pad5)") (class "Default")
      (node (ref "U4") (pin "5") (pinfunction "Z2_5") (pintype "output"))
    )
    (net (code "157") (name "unconnected-(U5A-B8-Pad11)") (class "Default")
      (node (ref "U5") (pin "11") (pinfunction "B8_11") (pintype "bidirectional"))
    )
    (net (code "158") (name "unconnected-(U6A-A8-Pad9)") (class "Default")
      (node (ref "U6") (pin "9") (pinfunction "A8_9") (pintype "bidirectional"))
    )
    (net (code "159") (name "unconnected-(X4-Pad1)") (class "Default")
      (node (ref "X4") (pin "1") (pinfunction "1_1") (pintype "passive"))
    )
    (net (code "160") (name "unconnected-(X4-Pad4)") (class "Default")
      (node (ref "X4") (pin "4") (pinfunction "4_4") (pintype "passive"))
    )
    (net (code "161") (name "unconnected-(X4-Pad6)") (class "Default")
      (node (ref "X4") (pin "6") (pinfunction "6_6") (pintype "passive"))
    )
    (net (code "162") (name "unconnected-(X4-Pad7)") (class "Default")
      (node (ref "X4") (pin "7") (pinfunction "7_7") (pintype "passive"))
    )
    (net (code "163") (name "unconnected-(X4-Pad8)") (class "Default")
      (node (ref "X4") (pin "8") (pinfunction "8_8") (pintype "passive"))
    )
    (net (code "164") (name "unconnected-(X4-Pad9)") (class "Default")
      (node (ref "X4") (pin "9") (pinfunction "9_9") (pintype "passive"))
    )
  )
)
